# untitled.net
KiCad netlist of a schematic drawn in EAGLE
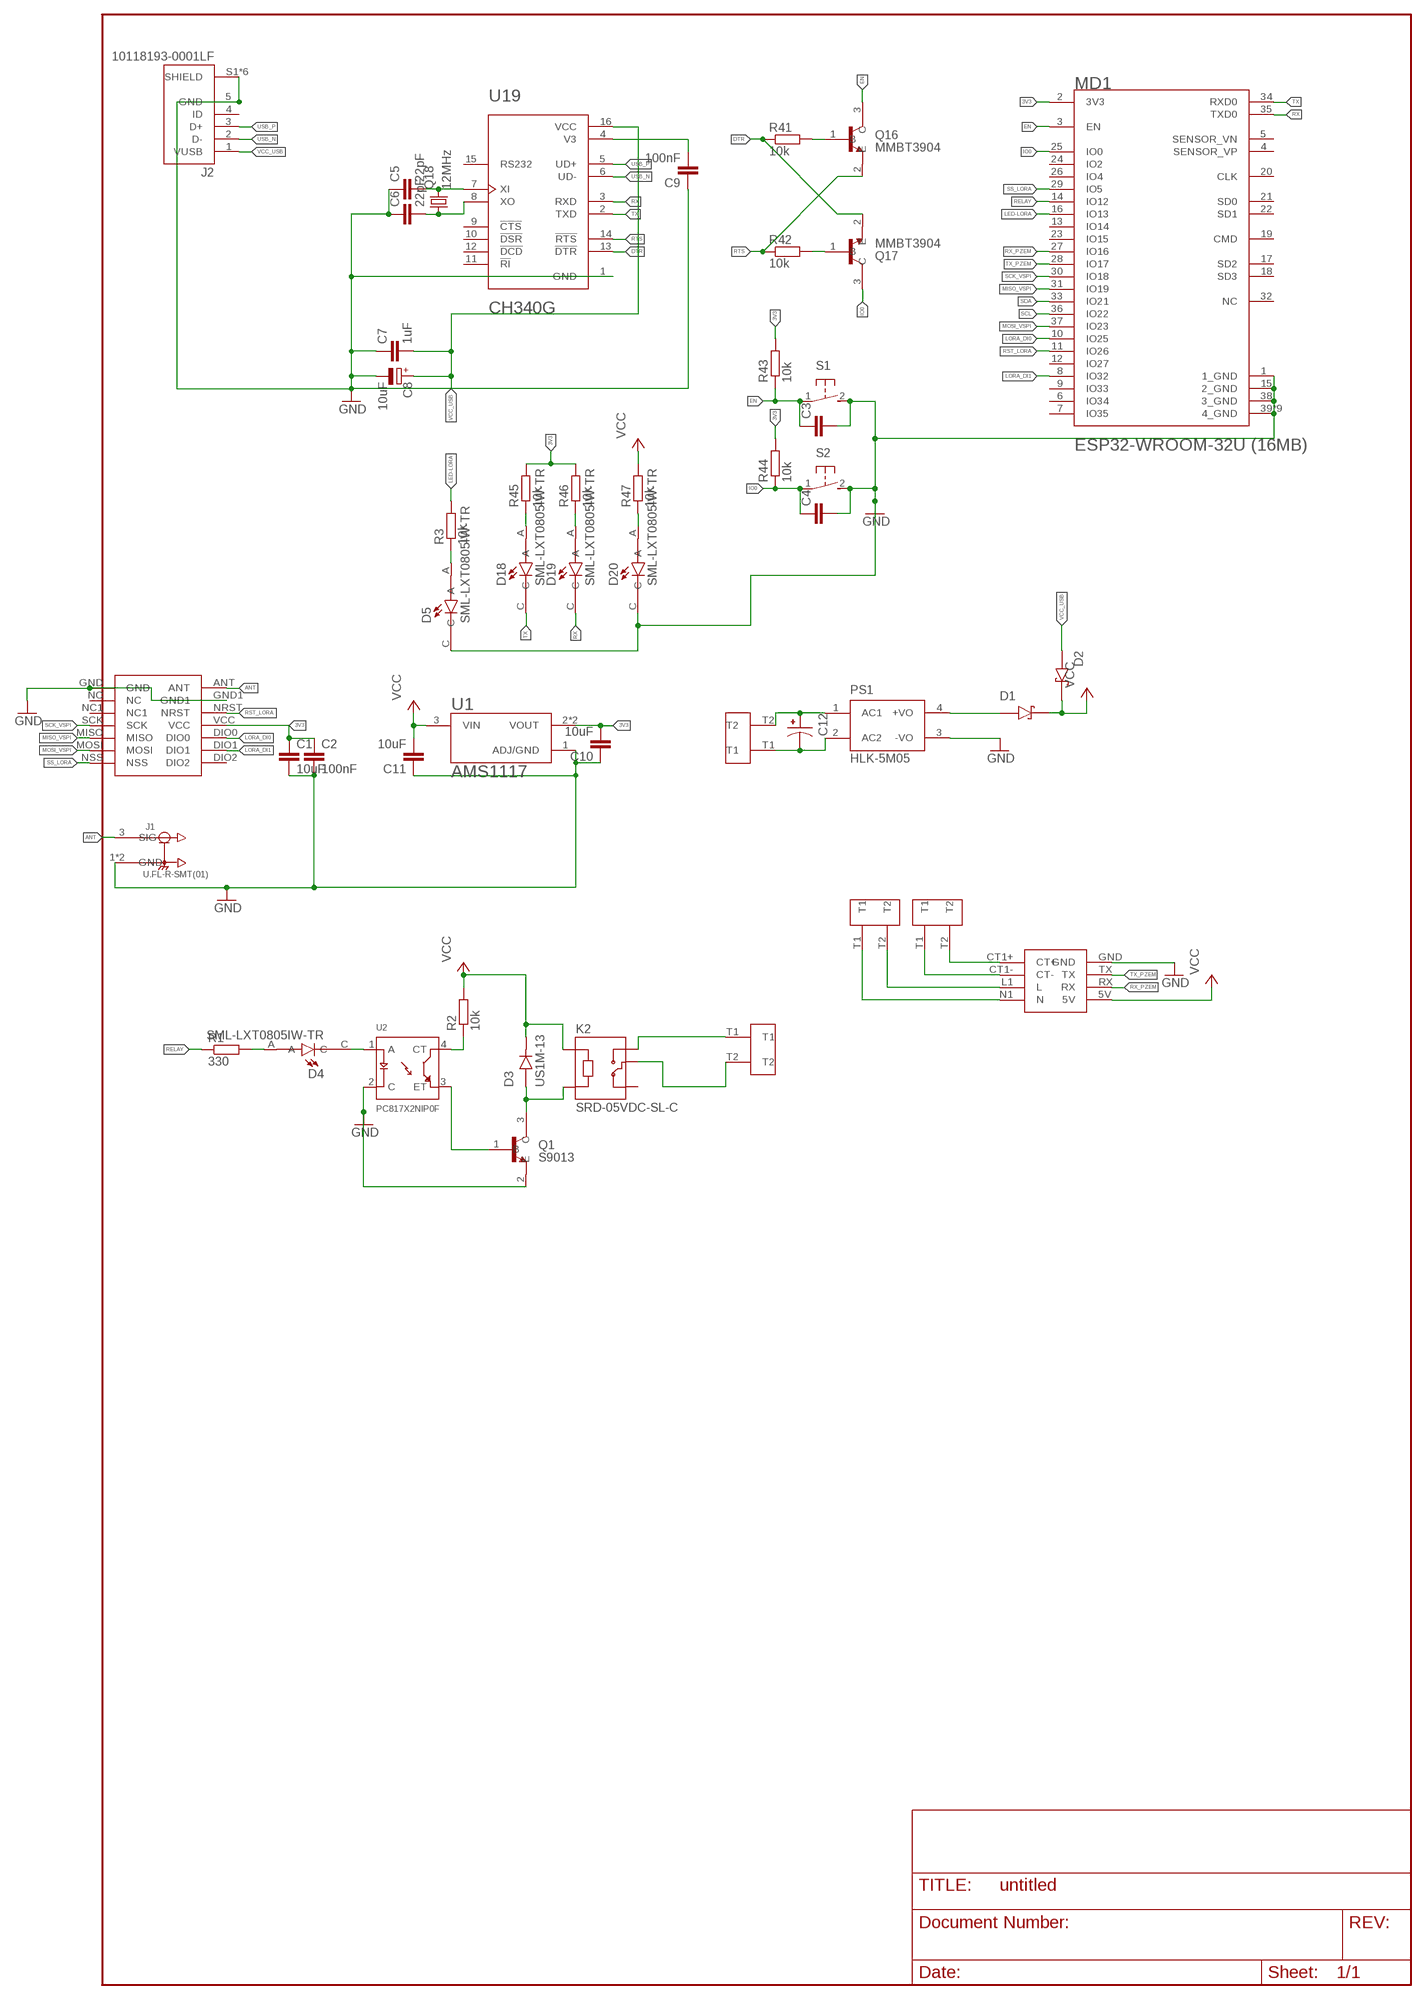
[diagram p0: schematic, sheet 1]

(export (version "E")
  (design (tool "Eeschema 10.0.6"))
  (components
    (comp (ref "C1")
      (value "10uF")
      (footprint "eagle-import:C0805K")
      (libsource (lib "eagle-import") (part "C-EUC0805K"))
    )
    (comp (ref "C2")
      (value "100nF")
      (footprint "eagle-import:C0805K")
      (libsource (lib "eagle-import") (part "C-EUC0805K"))
    )
    (comp (ref "C3")
      (value "C-EUC0805K")
      (footprint "eagle-import:C0805K")
      (libsource (lib "eagle-import") (part "C-EUC0805K"))
    )
    (comp (ref "C4")
      (value "C-EUC0805K")
      (footprint "eagle-import:C0805K")
      (libsource (lib "eagle-import") (part "C-EUC0805K"))
    )
    (comp (ref "C5")
      (value "22pF")
      (footprint "eagle-import:C0805K")
      (libsource (lib "eagle-import") (part "C-EUC0805K"))
    )
    (comp (ref "C6")
      (value "22pF")
      (footprint "eagle-import:C0805K")
      (libsource (lib "eagle-import") (part "C-EUC0805K"))
    )
    (comp (ref "C7")
      (value "1uF")
      (footprint "eagle-import:C0805K")
      (libsource (lib "eagle-import") (part "C-EUC0805K"))
    )
    (comp (ref "C8")
      (value "10uF")
      (footprint "eagle-import:153CLV-0505")
      (libsource (lib "eagle-import") (part "CPOL-EU153CLV-0505"))
    )
    (comp (ref "C9")
      (value "100nF")
      (footprint "eagle-import:C0805K")
      (libsource (lib "eagle-import") (part "C-EUC0805K"))
    )
    (comp (ref "C10")
      (value "10uF")
      (footprint "eagle-import:C0805K")
      (libsource (lib "eagle-import") (part "C-EUC0805K"))
    )
    (comp (ref "C11")
      (value "10uF")
      (footprint "eagle-import:C0805K")
      (libsource (lib "eagle-import") (part "C-EUC0805K"))
    )
    (comp (ref "C12")
      (value "UPM2E100MHD1TO")
      (footprint "eagle-import:CAPPRD500W60D1250H2200")
      (fields (field (name "MF") "Nichicon"))
      (libsource (lib "eagle-import") (part "UPM2E100MHD1TO"))
    )
    (comp (ref "D1")
      (value "1N5819HW-7")
      (footprint "eagle-import:SOD3715X145N")
      (fields (field (name "MF") "Diodes Inc."))
      (libsource (lib "eagle-import") (part "1N5819HW-7"))
    )
    (comp (ref "D2")
      (value "1N5819HW-7")
      (footprint "eagle-import:SOD3715X145N")
      (fields (field (name "MF") "Diodes Inc."))
      (libsource (lib "eagle-import") (part "1N5819HW-7"))
    )
    (comp (ref "D3")
      (value "US1M-13")
      (footprint "eagle-import:DIOM5226X240N")
      (fields (field (name "MF") "Diodes Incorporated"))
      (libsource (lib "eagle-import") (part "US1M-13"))
    )
    (comp (ref "D4")
      (value "SML-LXT0805IW-TR")
      (footprint "eagle-import:LEDC2012X120N")
      (fields (field (name "MF") "Lumex Opto/Components"))
      (libsource (lib "eagle-import") (part "SML-LXT0805IW-TR"))
    )
    (comp (ref "D5")
      (value "SML-LXT0805IW-TR")
      (footprint "eagle-import:LEDC2012X120N")
      (fields (field (name "MF") "Lumex Opto/Components"))
      (libsource (lib "eagle-import") (part "SML-LXT0805IW-TR"))
    )
    (comp (ref "D18")
      (value "SML-LXT0805IW-TR")
      (footprint "eagle-import:LEDC2012X120N")
      (fields (field (name "MF") "Lumex Opto/Components"))
      (libsource (lib "eagle-import") (part "SML-LXT0805IW-TR"))
    )
    (comp (ref "D19")
      (value "SML-LXT0805IW-TR")
      (footprint "eagle-import:LEDC2012X120N")
      (fields (field (name "MF") "Lumex Opto/Components"))
      (libsource (lib "eagle-import") (part "SML-LXT0805IW-TR"))
    )
    (comp (ref "D20")
      (value "SML-LXT0805IW-TR")
      (footprint "eagle-import:LEDC2012X120N")
      (fields (field (name "MF") "Lumex Opto/Components"))
      (libsource (lib "eagle-import") (part "SML-LXT0805IW-TR"))
    )
    (comp (ref "J1")
      (value "U.FL-R-SMT(01)")
      (footprint "eagle-import:HRS_U.FL-R-SMT(01)")
      (fields (field (name "MF") "Hirose"))
      (libsource (lib "eagle-import") (part "U.FL-R-SMT(01)"))
    )
    (comp (ref "J2")
      (value "10118193-0001LF")
      (footprint "eagle-import:FCI_10118193-0001LF")
      (fields (field (name "MF") "FCI"))
      (libsource (lib "eagle-import") (part "10118193-0001LF"))
    )
    (comp (ref "K2")
      (value "SRD-05VDC-SL-C")
      (footprint "eagle-import:RELAY_SRD-05VDC-SL-C")
      (fields (field (name "MF") "Songle Relay"))
      (libsource (lib "eagle-import") (part "SRD-05VDC-SL-C"))
    )
    (comp (ref "LORA-NICERF-V1")
      (value "LORA-NICERF-V2")
      (footprint "eagle-import:LORA-NICERF-V2")
      (libsource (lib "eagle-import") (part "LORA-NICERF-V2"))
    )
    (comp (ref "MD1")
      (value "ESPRESSIF_SYSTEMS_ESP32-WROOM-32U_16MBESPRESSIF_SYSTEMS_ESP32-WROOM-32U_16MB_0_0")
      (footprint "eagle-import:ESPRESSIF_SYSTEMS_ESP32-WROOM-32U_16MB_0")
      (fields
        (field (name "DIGIKEY_PART_NUMBER") "1904-1028-1-ND")
        (field (name "MF") "Espressif Systems")
        (field (name "MOUSER_PART_NUMBER") "356-ES32WROOM32U16MB")
      )
      (libsource (lib "eagle-import") (part "ESPRESSIF_SYSTEMS_ESP32-WROOM-32U_16MBESPRESSIF_SYSTEMS_ESP32-WROOM-32U_16MB_0_0"))
    )
    (comp (ref "PS1")
      (value "HLK-5M05")
      (footprint "eagle-import:CONV_HLK-5M05")
      (fields (field (name "MF") "Hi-link"))
      (libsource (lib "eagle-import") (part "HLK-5M05"))
    )
    (comp (ref "PZEM004T1")
      (value "PZEM004T")
      (footprint "eagle-import:PZEM004T")
      (libsource (lib "eagle-import") (part "PZEM004T"))
    )
    (comp (ref "Q1")
      (value "S9013")
      (footprint "eagle-import:SOT95P240X120-3N")
      (fields (field (name "MF") "JCET"))
      (libsource (lib "eagle-import") (part "S9013"))
    )
    (comp (ref "Q16")
      (value "MMBT3904")
      (footprint "eagle-import:SOT95P240X120-3N")
      (fields (field (name "MF") "ON Semiconductor"))
      (libsource (lib "eagle-import") (part "MMBT3904"))
    )
    (comp (ref "Q17")
      (value "MMBT3904")
      (footprint "eagle-import:SOT95P240X120-3N")
      (fields (field (name "MF") "ON Semiconductor"))
      (libsource (lib "eagle-import") (part "MMBT3904"))
    )
    (comp (ref "Q18")
      (value "12MHz")
      (footprint "eagle-import:SM49")
      (libsource (lib "eagle-import") (part "CRYSTALSM49"))
    )
    (comp (ref "R1")
      (value "330")
      (footprint "eagle-import:R0805")
      (libsource (lib "eagle-import") (part "R-EU_R0805"))
    )
    (comp (ref "R2")
      (value "10k")
      (footprint "eagle-import:R0805")
      (libsource (lib "eagle-import") (part "R-EU_R0805"))
    )
    (comp (ref "R3")
      (value "10k")
      (footprint "eagle-import:R0805")
      (libsource (lib "eagle-import") (part "R-EU_R0805"))
    )
    (comp (ref "R41")
      (value "10k")
      (footprint "eagle-import:R0805")
      (libsource (lib "eagle-import") (part "R-EU_R0805"))
    )
    (comp (ref "R42")
      (value "10k")
      (footprint "eagle-import:R0805")
      (libsource (lib "eagle-import") (part "R-EU_R0805"))
    )
    (comp (ref "R43")
      (value "10k")
      (footprint "eagle-import:R0805")
      (libsource (lib "eagle-import") (part "R-EU_R0805"))
    )
    (comp (ref "R44")
      (value "10k")
      (footprint "eagle-import:R0805")
      (libsource (lib "eagle-import") (part "R-EU_R0805"))
    )
    (comp (ref "R45")
      (value "10k")
      (footprint "eagle-import:R0805")
      (libsource (lib "eagle-import") (part "R-EU_R0805"))
    )
    (comp (ref "R46")
      (value "10k")
      (footprint "eagle-import:R0805")
      (libsource (lib "eagle-import") (part "R-EU_R0805"))
    )
    (comp (ref "R47")
      (value "10k")
      (footprint "eagle-import:R0805")
      (libsource (lib "eagle-import") (part "R-EU_R0805"))
    )
    (comp (ref "S1")
      (value "31-XX")
      (footprint "eagle-import:B3F-31XX")
      (fields (field (name "MPN") "B3F-3100"))
      (libsource (lib "eagle-import") (part "31-XX"))
    )
    (comp (ref "S2")
      (value "31-XX")
      (footprint "eagle-import:B3F-31XX")
      (fields (field (name "MPN") "B3F-3100"))
      (libsource (lib "eagle-import") (part "31-XX"))
    )
    (comp (ref "TB7.1")
      (value "TB7.62")
      (footprint "eagle-import:TB7.62")
      (libsource (lib "eagle-import") (part "TB7.62"))
    )
    (comp (ref "TB7.2")
      (value "TB7.62")
      (footprint "eagle-import:TB7.62")
      (libsource (lib "eagle-import") (part "TB7.62"))
    )
    (comp (ref "TB7.3")
      (value "TB7.62")
      (footprint "eagle-import:TB7.62")
      (libsource (lib "eagle-import") (part "TB7.62"))
    )
    (comp (ref "TB7.4")
      (value "TB7.62")
      (footprint "eagle-import:TB7.62")
      (libsource (lib "eagle-import") (part "TB7.62"))
    )
    (comp (ref "U1")
      (value "AMS1117")
      (footprint "eagle-import:SOT229P700X180-4N")
      (fields (field (name "MF") "Advanced Monolithic Systems"))
      (libsource (lib "eagle-import") (part "AMS1117"))
    )
    (comp (ref "U2")
      (value "PC817X2NIP0F")
      (footprint "eagle-import:SOT254P975X400-4N")
      (fields (field (name "MF") "Sharp Microelectronics"))
      (libsource (lib "eagle-import") (part "PC817X2NIP0F"))
    )
    (comp (ref "U19")
      (value "CH340G")
      (footprint "eagle-import:SOIC127P600X180-16N")
      (fields (field (name "MF") "WCH") (field (name "MP") "Ch340G"))
      (libsource (lib "eagle-import") (part "CH340G"))
    )
  )
  (nets
    (net (code "1") (name "3V3") (class "Default")
      (node (ref "C1") (pin "1") (pinfunction "1_1") (pintype "passive"))
      (node (ref "C10") (pin "2") (pinfunction "2_2") (pintype "passive"))
      (node (ref "C2") (pin "1") (pinfunction "1_1") (pintype "passive"))
      (node (ref "LORA-NICERF-V1") (pin "VCC") (pinfunction "VCC_VCC") (pintype "bidirectional"))
      (node (ref "MD1") (pin "2") (pinfunction "3V3_2") (pintype "power_in"))
      (node (ref "R43") (pin "2") (pinfunction "2_2") (pintype "passive"))
      (node (ref "R44") (pin "2") (pinfunction "2_2") (pintype "passive"))
      (node (ref "R45") (pin "2") (pinfunction "2_2") (pintype "passive"))
      (node (ref "R46") (pin "2") (pinfunction "2_2") (pintype "passive"))
      (node (ref "U1") (pin "2") (pinfunction "VOUT_2") (pintype "output"))
      (node (ref "U1") (pin "4") (pinfunction "VOUT_4") (pintype "output"))
    )
    (net (code "2") (name "ANT") (class "Default")
      (node (ref "J1") (pin "3") (pinfunction "SIG_3") (pintype "passive"))
      (node (ref "LORA-NICERF-V1") (pin "ANT") (pinfunction "ANT_ANT") (pintype "bidirectional"))
    )
    (net (code "3") (name "DTR") (class "Default")
      (node (ref "Q17") (pin "2") (pinfunction "E_2") (pintype "passive"))
      (node (ref "R41") (pin "1") (pinfunction "1_1") (pintype "passive"))
      (node (ref "U19") (pin "13") (pinfunction "~{DTR}_13") (pintype "output"))
    )
    (net (code "4") (name "EN") (class "Default")
      (node (ref "C3") (pin "1") (pinfunction "1_1") (pintype "passive"))
      (node (ref "MD1") (pin "3") (pinfunction "EN_3") (pintype "input"))
      (node (ref "Q16") (pin "3") (pinfunction "C_3") (pintype "passive"))
      (node (ref "R43") (pin "1") (pinfunction "1_1") (pintype "passive"))
      (node (ref "S1") (pin "1") (pinfunction "P_1") (pintype "passive"))
    )
    (net (code "5") (name "GND") (class "Default")
      (node (ref "C1") (pin "2") (pinfunction "2_2") (pintype "passive"))
      (node (ref "C10") (pin "1") (pinfunction "1_1") (pintype "passive"))
      (node (ref "C11") (pin "1") (pinfunction "1_1") (pintype "passive"))
      (node (ref "C2") (pin "2") (pinfunction "2_2") (pintype "passive"))
      (node (ref "C3") (pin "2") (pinfunction "2_2") (pintype "passive"))
      (node (ref "C4") (pin "2") (pinfunction "2_2") (pintype "passive"))
      (node (ref "C5") (pin "1") (pinfunction "1_1") (pintype "passive"))
      (node (ref "C6") (pin "1") (pinfunction "1_1") (pintype "passive"))
      (node (ref "C7") (pin "1") (pinfunction "1_1") (pintype "passive"))
      (node (ref "C8") (pin "-") (pinfunction "-_-") (pintype "passive"))
      (node (ref "C9") (pin "1") (pinfunction "1_1") (pintype "passive"))
      (node (ref "D20") (pin "C") (pinfunction "C_C") (pintype "passive"))
      (node (ref "D5") (pin "C") (pinfunction "C_C") (pintype "passive"))
      (node (ref "J1") (pin "1") (pinfunction "GND_1") (pintype "passive"))
      (node (ref "J1") (pin "2") (pinfunction "GND_2") (pintype "passive"))
      (node (ref "J2") (pin "5") (pinfunction "GND_5") (pintype "passive"))
      (node (ref "J2") (pin "S1") (pinfunction "SHIELD_S1") (pintype "passive"))
      (node (ref "J2") (pin "S2") (pinfunction "SHIELD_S2") (pintype "passive"))
      (node (ref "J2") (pin "S3") (pinfunction "SHIELD_S3") (pintype "passive"))
      (node (ref "J2") (pin "S4") (pinfunction "SHIELD_S4") (pintype "passive"))
      (node (ref "J2") (pin "S5") (pinfunction "SHIELD_S5") (pintype "passive"))
      (node (ref "J2") (pin "S6") (pinfunction "SHIELD_S6") (pintype "passive"))
      (node (ref "LORA-NICERF-V1") (pin "GND") (pinfunction "GND_GND") (pintype "bidirectional"))
      (node (ref "LORA-NICERF-V1") (pin "GND1") (pinfunction "GND1_GND1") (pintype "bidirectional"))
      (node (ref "MD1") (pin "1") (pinfunction "1_GND_1") (pintype "power_in"))
      (node (ref "MD1") (pin "15") (pinfunction "2_GND_15") (pintype "power_in"))
      (node (ref "MD1") (pin "38") (pinfunction "3_GND_38") (pintype "power_in"))
      (node (ref "MD1") (pin "39") (pinfunction "4_GND_39") (pintype "power_in"))
      (node (ref "MD1") (pin "39-2") (pinfunction "4_GND_39-2") (pintype "power_in"))
      (node (ref "MD1") (pin "39-3") (pinfunction "4_GND_39-3") (pintype "power_in"))
      (node (ref "MD1") (pin "39-4") (pinfunction "4_GND_39-4") (pintype "power_in"))
      (node (ref "MD1") (pin "39-5") (pinfunction "4_GND_39-5") (pintype "power_in"))
      (node (ref "MD1") (pin "39-6") (pinfunction "4_GND_39-6") (pintype "power_in"))
      (node (ref "MD1") (pin "39-7") (pinfunction "4_GND_39-7") (pintype "power_in"))
      (node (ref "MD1") (pin "39-8") (pinfunction "4_GND_39-8") (pintype "power_in"))
      (node (ref "MD1") (pin "39-9") (pinfunction "4_GND_39-9") (pintype "power_in"))
      (node (ref "PS1") (pin "3") (pinfunction "-VO_3") (pintype "output"))
      (node (ref "PZEM004T1") (pin "GND") (pinfunction "GND_GND") (pintype "bidirectional"))
      (node (ref "Q1") (pin "2") (pinfunction "E_2") (pintype "passive"))
      (node (ref "S1") (pin "2") (pinfunction "S_2") (pintype "passive"))
      (node (ref "S2") (pin "2") (pinfunction "S_2") (pintype "passive"))
      (node (ref "U1") (pin "1") (pinfunction "ADJ/GND_1") (pintype "power_in"))
      (node (ref "U19") (pin "1") (pinfunction "GND_1") (pintype "power_in"))
      (node (ref "U2") (pin "2") (pinfunction "C_2") (pintype "passive"))
    )
    (net (code "6") (name "IO0") (class "Default")
      (node (ref "C4") (pin "1") (pinfunction "1_1") (pintype "passive"))
      (node (ref "MD1") (pin "25") (pinfunction "IO0_25") (pintype "bidirectional"))
      (node (ref "Q17") (pin "3") (pinfunction "C_3") (pintype "passive"))
      (node (ref "R44") (pin "1") (pinfunction "1_1") (pintype "passive"))
      (node (ref "S2") (pin "1") (pinfunction "P_1") (pintype "passive"))
    )
    (net (code "7") (name "LED-LORA") (class "Default")
      (node (ref "MD1") (pin "16") (pinfunction "IO13_16") (pintype "bidirectional"))
      (node (ref "R3") (pin "2") (pinfunction "2_2") (pintype "passive"))
    )
    (net (code "8") (name "LORA_DI0") (class "Default")
      (node (ref "LORA-NICERF-V1") (pin "DIO0") (pinfunction "DIO0_DIO0") (pintype "bidirectional"))
      (node (ref "MD1") (pin "10") (pinfunction "IO25_10") (pintype "bidirectional"))
    )
    (net (code "9") (name "LORA_DI1") (class "Default")
      (node (ref "LORA-NICERF-V1") (pin "DIO1") (pinfunction "DIO1_DIO1") (pintype "bidirectional"))
      (node (ref "MD1") (pin "8") (pinfunction "IO32_8") (pintype "bidirectional"))
    )
    (net (code "10") (name "MISO_VSPI") (class "Default")
      (node (ref "LORA-NICERF-V1") (pin "MISO") (pinfunction "MISO_MISO") (pintype "bidirectional"))
      (node (ref "MD1") (pin "31") (pinfunction "IO19_31") (pintype "bidirectional"))
    )
    (net (code "11") (name "MOSI_VSPI") (class "Default")
      (node (ref "LORA-NICERF-V1") (pin "MOSI") (pinfunction "MOSI_MOSI") (pintype "bidirectional"))
      (node (ref "MD1") (pin "37") (pinfunction "IO23_37") (pintype "bidirectional"))
    )
    (net (code "12") (name "Net-(D4-PadA)") (class "Default")
      (node (ref "D4") (pin "A") (pinfunction "A_A") (pintype "passive"))
      (node (ref "R1") (pin "2") (pinfunction "2_2") (pintype "passive"))
    )
    (net (code "13") (name "Net-(D5-PadA)") (class "Default")
      (node (ref "D5") (pin "A") (pinfunction "A_A") (pintype "passive"))
      (node (ref "R3") (pin "1") (pinfunction "1_1") (pintype "passive"))
    )
    (net (code "14") (name "Net-(D18-PadA)") (class "Default")
      (node (ref "D18") (pin "A") (pinfunction "A_A") (pintype "passive"))
      (node (ref "R45") (pin "1") (pinfunction "1_1") (pintype "passive"))
    )
    (net (code "15") (name "Net-(D19-PadA)") (class "Default")
      (node (ref "D19") (pin "A") (pinfunction "A_A") (pintype "passive"))
      (node (ref "R46") (pin "1") (pinfunction "1_1") (pintype "passive"))
    )
    (net (code "16") (name "Net-(D20-PadA)") (class "Default")
      (node (ref "D20") (pin "A") (pinfunction "A_A") (pintype "passive"))
      (node (ref "R47") (pin "1") (pinfunction "1_1") (pintype "passive"))
    )
    (net (code "17") (name "Net-(K2-PadCOM)") (class "Default")
      (node (ref "K2") (pin "COM") (pinfunction "COM_COM") (pintype "passive"))
      (node (ref "TB7.2") (pin "T2") (pinfunction "T2_T2") (pintype "bidirectional"))
    )
    (net (code "18") (name "Net-(K2-PadNO)") (class "Default")
      (node (ref "K2") (pin "NO") (pinfunction "NO_NO") (pintype "passive"))
      (node (ref "TB7.2") (pin "T1") (pinfunction "T1_T1") (pintype "bidirectional"))
    )
    (net (code "19") (name "Net-(PS1-+VO)") (class "Default")
      (node (ref "D1") (pin "A") (pinfunction "A_A") (pintype "passive"))
      (node (ref "PS1") (pin "4") (pinfunction "+VO_4") (pintype "output"))
    )
    (net (code "20") (name "Net-(PS1-AC1)") (class "Default")
      (node (ref "C12") (pin "P") (pinfunction "P_P") (pintype "passive"))
      (node (ref "PS1") (pin "1") (pinfunction "AC1_1") (pintype "input"))
      (node (ref "TB7.1") (pin "T2") (pinfunction "T2_T2") (pintype "bidirectional"))
    )
    (net (code "21") (name "Net-(PS1-AC2)") (class "Default")
      (node (ref "C12") (pin "N") (pinfunction "N_N") (pintype "passive"))
      (node (ref "PS1") (pin "2") (pinfunction "AC2_2") (pintype "input"))
      (node (ref "TB7.1") (pin "T1") (pinfunction "T1_T1") (pintype "bidirectional"))
    )
    (net (code "22") (name "Net-(PZEM004T1-CT+)") (class "Default")
      (node (ref "PZEM004T1") (pin "CT1+") (pinfunction "CT+_CT1+") (pintype "bidirectional"))
      (node (ref "TB7.3") (pin "T2") (pinfunction "T2_T2") (pintype "bidirectional"))
    )
    (net (code "23") (name "Net-(PZEM004T1-CT-)") (class "Default")
      (node (ref "PZEM004T1") (pin "CT1-") (pinfunction "CT-_CT1-") (pintype "bidirectional"))
      (node (ref "TB7.3") (pin "T1") (pinfunction "T1_T1") (pintype "bidirectional"))
    )
    (net (code "24") (name "Net-(PZEM004T1-L)") (class "Default")
      (node (ref "PZEM004T1") (pin "L1") (pinfunction "L_L1") (pintype "bidirectional"))
      (node (ref "TB7.4") (pin "T2") (pinfunction "T2_T2") (pintype "bidirectional"))
    )
    (net (code "25") (name "Net-(PZEM004T1-N)") (class "Default")
      (node (ref "PZEM004T1") (pin "N1") (pinfunction "N_N1") (pintype "bidirectional"))
      (node (ref "TB7.4") (pin "T1") (pinfunction "T1_T1") (pintype "bidirectional"))
    )
    (net (code "26") (name "Net-(Q1-B)") (class "Default")
      (node (ref "Q1") (pin "1") (pinfunction "B_1") (pintype "passive"))
      (node (ref "U2") (pin "3") (pinfunction "ET_3") (pintype "passive"))
    )
    (net (code "27") (name "Net-(Q1-C)") (class "Default")
      (node (ref "D3") (pin "A") (pinfunction "A_A") (pintype "passive"))
      (node (ref "K2") (pin "A2") (pinfunction "A2_A2") (pintype "passive"))
      (node (ref "Q1") (pin "3") (pinfunction "C_3") (pintype "passive"))
    )
    (net (code "28") (name "Net-(Q16-B)") (class "Default")
      (node (ref "Q16") (pin "1") (pinfunction "B_1") (pintype "passive"))
      (node (ref "R41") (pin "2") (pinfunction "2_2") (pintype "passive"))
    )
    (net (code "29") (name "Net-(Q17-B)") (class "Default")
      (node (ref "Q17") (pin "1") (pinfunction "B_1") (pintype "passive"))
      (node (ref "R42") (pin "2") (pinfunction "2_2") (pintype "passive"))
    )
    (net (code "30") (name "Net-(U2-A)") (class "Default")
      (node (ref "D4") (pin "C") (pinfunction "C_C") (pintype "passive"))
      (node (ref "U2") (pin "1") (pinfunction "A_1") (pintype "passive"))
    )
    (net (code "31") (name "Net-(U2-CT)") (class "Default")
      (node (ref "R2") (pin "1") (pinfunction "1_1") (pintype "passive"))
      (node (ref "U2") (pin "4") (pinfunction "CT_4") (pintype "passive"))
    )
    (net (code "32") (name "Net-(U19-V3)") (class "Default")
      (node (ref "C9") (pin "2") (pinfunction "2_2") (pintype "passive"))
      (node (ref "U19") (pin "4") (pinfunction "V3_4") (pintype "power_in"))
    )
    (net (code "33") (name "Net-(U19-XI)") (class "Default")
      (node (ref "C5") (pin "2") (pinfunction "2_2") (pintype "passive"))
      (node (ref "Q18") (pin "2") (pinfunction "2_2") (pintype "passive"))
      (node (ref "U19") (pin "7") (pinfunction "XI_7") (pintype "input"))
    )
    (net (code "34") (name "Net-(U19-XO)") (class "Default")
      (node (ref "C6") (pin "2") (pinfunction "2_2") (pintype "passive"))
      (node (ref "Q18") (pin "1") (pinfunction "1_1") (pintype "passive"))
      (node (ref "U19") (pin "8") (pinfunction "XO_8") (pintype "output"))
    )
    (net (code "35") (name "RELAY") (class "Default")
      (node (ref "MD1") (pin "14") (pinfunction "IO12_14") (pintype "bidirectional"))
      (node (ref "R1") (pin "1") (pinfunction "1_1") (pintype "passive"))
    )
    (net (code "36") (name "RST_LORA") (class "Default")
      (node (ref "LORA-NICERF-V1") (pin "NRST") (pinfunction "NRST_NRST") (pintype "bidirectional"))
      (node (ref "MD1") (pin "11") (pinfunction "IO26_11") (pintype "bidirectional"))
    )
    (net (code "37") (name "RTS") (class "Default")
      (node (ref "Q16") (pin "2") (pinfunction "E_2") (pintype "passive"))
      (node (ref "R42") (pin "1") (pinfunction "1_1") (pintype "passive"))
      (node (ref "U19") (pin "14") (pinfunction "~{RTS}_14") (pintype "output"))
    )
    (net (code "38") (name "RX") (class "Default")
      (node (ref "D19") (pin "C") (pinfunction "C_C") (pintype "passive"))
      (node (ref "MD1") (pin "35") (pinfunction "TXD0_35") (pintype "bidirectional"))
      (node (ref "U19") (pin "3") (pinfunction "RXD_3") (pintype "input"))
    )
    (net (code "39") (name "RX_PZEM") (class "Default")
      (node (ref "MD1") (pin "27") (pinfunction "IO16_27") (pintype "bidirectional"))
      (node (ref "PZEM004T1") (pin "RX") (pinfunction "RX_RX") (pintype "bidirectional"))
    )
    (net (code "40") (name "SCK_VSPI") (class "Default")
      (node (ref "LORA-NICERF-V1") (pin "SCK") (pinfunction "SCK_SCK") (pintype "bidirectional"))
      (node (ref "MD1") (pin "30") (pinfunction "IO18_30") (pintype "bidirectional"))
    )
    (net (code "41") (name "SCL") (class "Default")
      (node (ref "MD1") (pin "36") (pinfunction "IO22_36") (pintype "bidirectional"))
    )
    (net (code "42") (name "SDA") (class "Default")
      (node (ref "MD1") (pin "33") (pinfunction "IO21_33") (pintype "bidirectional"))
    )
    (net (code "43") (name "SS_LORA") (class "Default")
      (node (ref "LORA-NICERF-V1") (pin "NSS") (pinfunction "NSS_NSS") (pintype "bidirectional"))
      (node (ref "MD1") (pin "29") (pinfunction "IO5_29") (pintype "bidirectional"))
    )
    (net (code "44") (name "TX") (class "Default")
      (node (ref "D18") (pin "C") (pinfunction "C_C") (pintype "passive"))
      (node (ref "MD1") (pin "34") (pinfunction "RXD0_34") (pintype "bidirectional"))
      (node (ref "U19") (pin "2") (pinfunction "TXD_2") (pintype "output"))
    )
    (net (code "45") (name "TX_PZEM") (class "Default")
      (node (ref "MD1") (pin "28") (pinfunction "IO17_28") (pintype "bidirectional"))
      (node (ref "PZEM004T1") (pin "TX") (pinfunction "TX_TX") (pintype "bidirectional"))
    )
    (net (code "46") (name "USB_N") (class "Default")
      (node (ref "J2") (pin "2") (pinfunction "D-_2") (pintype "passive"))
      (node (ref "U19") (pin "6") (pinfunction "UD-_6") (pintype "bidirectional"))
    )
    (net (code "47") (name "USB_P") (class "Default")
      (node (ref "J2") (pin "3") (pinfunction "D+_3") (pintype "passive"))
      (node (ref "U19") (pin "5") (pinfunction "UD+_5") (pintype "bidirectional"))
    )
    (net (code "48") (name "VCC") (class "Default")
      (node (ref "C11") (pin "2") (pinfunction "2_2") (pintype "passive"))
      (node (ref "D1") (pin "C") (pinfunction "K_C") (pintype "passive"))
      (node (ref "D2") (pin "C") (pinfunction "K_C") (pintype "passive"))
      (node (ref "D3") (pin "C") (pinfunction "K_C") (pintype "passive"))
      (node (ref "K2") (pin "A1") (pinfunction "A1_A1") (pintype "passive"))
      (node (ref "PZEM004T1") (pin "5V") (pinfunction "5V_5V") (pintype "bidirectional"))
      (node (ref "R2") (pin "2") (pinfunction "2_2") (pintype "passive"))
      (node (ref "R47") (pin "2") (pinfunction "2_2") (pintype "passive"))
      (node (ref "U1") (pin "3") (pinfunction "VIN_3") (pintype "input"))
    )
    (net (code "49") (name "VCC_USB") (class "Default")
      (node (ref "C7") (pin "2") (pinfunction "2_2") (pintype "passive"))
      (node (ref "C8") (pin "+") (pinfunction "+_+") (pintype "passive"))
      (node (ref "D2") (pin "A") (pinfunction "A_A") (pintype "passive"))
      (node (ref "J2") (pin "1") (pinfunction "VUSB_1") (pintype "passive"))
      (node (ref "U19") (pin "16") (pinfunction "VCC_16") (pintype "power_in"))
    )
    (net (code "50") (name "unconnected-(J2-ID-Pad4)") (class "Default")
      (node (ref "J2") (pin "4") (pinfunction "ID_4") (pintype "passive"))
    )
    (net (code "51") (name "unconnected-(K2-PadNC)") (class "Default")
      (node (ref "K2") (pin "NC") (pinfunction "NC_NC") (pintype "passive"))
    )
    (net (code "52") (name "unconnected-(LORA-NICERF-V1-PadDIO2)") (class "Default")
      (node (ref "LORA-NICERF-V1") (pin "DIO2") (pinfunction "DIO2_DIO2") (pintype "bidirectional"))
    )
    (net (code "53") (name "unconnected-(LORA-NICERF-V1-PadNC)") (class "Default")
      (node (ref "LORA-NICERF-V1") (pin "NC") (pinfunction "NC_NC") (pintype "bidirectional"))
    )
    (net (code "54") (name "unconnected-(LORA-NICERF-V1-PadNC1)") (class "Default")
      (node (ref "LORA-NICERF-V1") (pin "NC1") (pinfunction "NC1_NC1") (pintype "bidirectional"))
    )
    (net (code "55") (name "unconnected-(MD1-CLK-Pad20)") (class "Default")
      (node (ref "MD1") (pin "20") (pinfunction "CLK_20") (pintype "bidirectional"))
    )
    (net (code "56") (name "unconnected-(MD1-CMD-Pad19)") (class "Default")
      (node (ref "MD1") (pin "19") (pinfunction "CMD_19") (pintype "bidirectional"))
    )
    (net (code "57") (name "unconnected-(MD1-IO2-Pad24)") (class "Default")
      (node (ref "MD1") (pin "24") (pinfunction "IO2_24") (pintype "bidirectional"))
    )
    (net (code "58") (name "unconnected-(MD1-IO4-Pad26)") (class "Default")
      (node (ref "MD1") (pin "26") (pinfunction "IO4_26") (pintype "bidirectional"))
    )
    (net (code "59") (name "unconnected-(MD1-IO14-Pad13)") (class "Default")
      (node (ref "MD1") (pin "13") (pinfunction "IO14_13") (pintype "bidirectional"))
    )
    (net (code "60") (name "unconnected-(MD1-IO15-Pad23)") (class "Default")
      (node (ref "MD1") (pin "23") (pinfunction "IO15_23") (pintype "bidirectional"))
    )
    (net (code "61") (name "unconnected-(MD1-IO27-Pad12)") (class "Default")
      (node (ref "MD1") (pin "12") (pinfunction "IO27_12") (pintype "bidirectional"))
    )
    (net (code "62") (name "unconnected-(MD1-IO33-Pad9)") (class "Default")
      (node (ref "MD1") (pin "9") (pinfunction "IO33_9") (pintype "bidirectional"))
    )
    (net (code "63") (name "unconnected-(MD1-IO34-Pad6)") (class "Default")
      (node (ref "MD1") (pin "6") (pinfunction "IO34_6") (pintype "bidirectional"))
    )
    (net (code "64") (name "unconnected-(MD1-IO35-Pad7)") (class "Default")
      (node (ref "MD1") (pin "7") (pinfunction "IO35_7") (pintype "bidirectional"))
    )
    (net (code "65") (name "unconnected-(MD1-NC-Pad32)") (class "Default")
      (node (ref "MD1") (pin "32") (pinfunction "NC_32") (pintype "passive"))
    )
    (net (code "66") (name "unconnected-(MD1-SD0-Pad21)") (class "Default")
      (node (ref "MD1") (pin "21") (pinfunction "SD0_21") (pintype "bidirectional"))
    )
    (net (code "67") (name "unconnected-(MD1-SD1-Pad22)") (class "Default")
      (node (ref "MD1") (pin "22") (pinfunction "SD1_22") (pintype "bidirectional"))
    )
    (net (code "68") (name "unconnected-(MD1-SD2-Pad17)") (class "Default")
      (node (ref "MD1") (pin "17") (pinfunction "SD2_17") (pintype "bidirectional"))
    )
    (net (code "69") (name "unconnected-(MD1-SD3-Pad18)") (class "Default")
      (node (ref "MD1") (pin "18") (pinfunction "SD3_18") (pintype "bidirectional"))
    )
    (net (code "70") (name "unconnected-(MD1-SENSOR_VN-Pad5)") (class "Default")
      (node (ref "MD1") (pin "5") (pinfunction "SENSOR_VN_5") (pintype "input"))
    )
    (net (code "71") (name "unconnected-(MD1-SENSOR_VP-Pad4)") (class "Default")
      (node (ref "MD1") (pin "4") (pinfunction "SENSOR_VP_4") (pintype "input"))
    )
    (net (code "72") (name "unconnected-(U19-RS232-Pad15)") (class "Default")
      (node (ref "U19") (pin "15") (pinfunction "RS232_15") (pintype "input"))
    )
    (net (code "73") (name "unconnected-(U19-~{CTS}-Pad9)") (class "Default")
      (node (ref "U19") (pin "9") (pinfunction "~{CTS}_9") (pintype "input"))
    )
    (net (code "74") (name "unconnected-(U19-~{DCD}-Pad12)") (class "Default")
      (node (ref "U19") (pin "12") (pinfunction "~{DCD}_12") (pintype "input"))
    )
    (net (code "75") (name "unconnected-(U19-~{DSR}-Pad10)") (class "Default")
      (node (ref "U19") (pin "10") (pinfunction "~{DSR}_10") (pintype "input"))
    )
    (net (code "76") (name "unconnected-(U19-~{RI}-Pad11)") (class "Default")
      (node (ref "U19") (pin "11") (pinfunction "~{RI}_11") (pintype "input"))
    )
  )
)
